# schematic.net
KiCad netlist of a schematic drawn in EAGLE
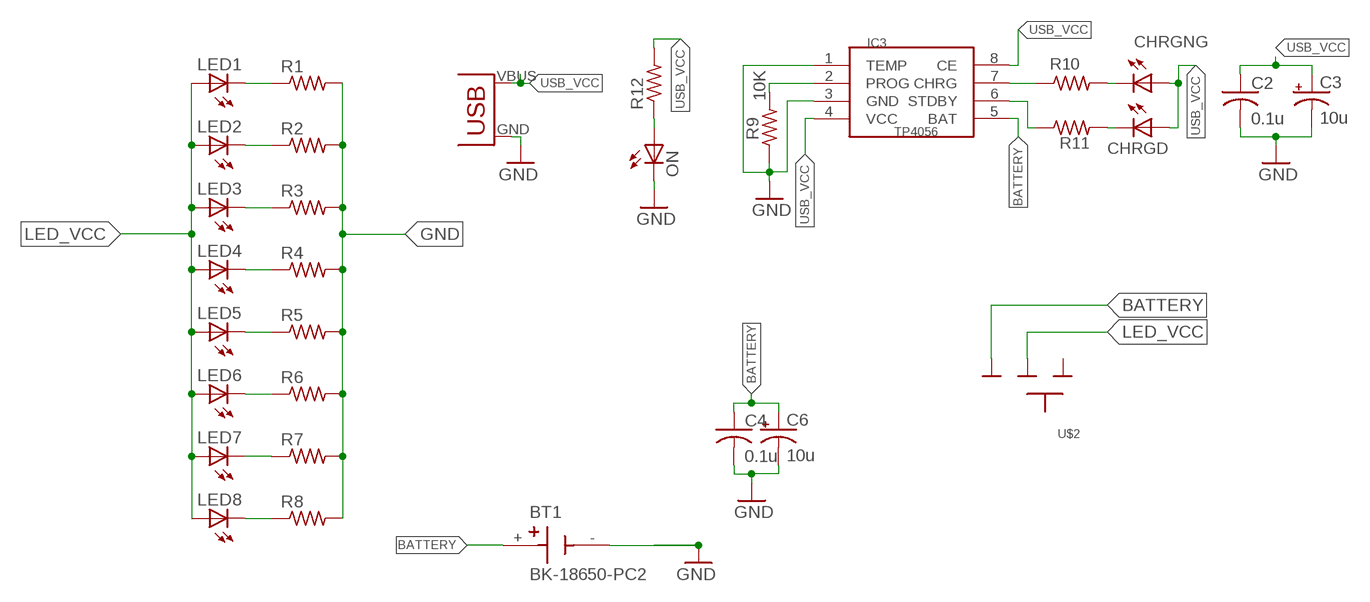
[diagram p0: schematic, sheet 1]

(export (version "E")
  (design (tool "Eeschema 10.0.6"))
  (components
    (comp (ref "BT1")
      (value "BK-18650-PC2")
      (footprint "eagle-import:BAT_BK-18650-PC2")
      (fields (field (name "MF") "MPD (Memory Protection Devices)"))
      (libsource (lib "eagle-import") (part "BK-18650-PC2"))
    )
    (comp (ref "C2")
      (value "0.1u")
      (footprint "eagle-import:C0805")
      (libsource (lib "eagle-import") (part "CAP0805"))
    )
    (comp (ref "C3")
      (value "10u")
      (footprint "eagle-import:B_3528-21R")
      (libsource (lib "eagle-import") (part "CAP_POL_16V"))
    )
    (comp (ref "C4")
      (value "0.1u")
      (footprint "eagle-import:C0805")
      (libsource (lib "eagle-import") (part "CAP0805"))
    )
    (comp (ref "C6")
      (value "10u")
      (footprint "eagle-import:B_3528-21R")
      (libsource (lib "eagle-import") (part "CAP_POL_16V"))
    )
    (comp (ref "CHRGD")
      (value "LED3MM")
      (footprint "eagle-import:LED3MM")
      (libsource (lib "eagle-import") (part "LED3MM"))
    )
    (comp (ref "CHRGNG")
      (value "LED3MM")
      (footprint "eagle-import:LED3MM")
      (libsource (lib "eagle-import") (part "LED3MM"))
    )
    (comp (ref "IC3")
      (value "TP4056")
      (footprint "eagle-import:SOP-8")
      (libsource (lib "eagle-import") (part "TP4056"))
    )
    (comp (ref "LED1")
      (value "LED5MM")
      (footprint "eagle-import:LED5MM")
      (libsource (lib "eagle-import") (part "CEDT_JANUARY_2015_v6_LED5MM"))
    )
    (comp (ref "LED2")
      (value "LED5MM")
      (footprint "eagle-import:LED5MM")
      (libsource (lib "eagle-import") (part "CEDT_JANUARY_2015_v6_LED5MM"))
    )
    (comp (ref "LED3")
      (value "LED5MM")
      (footprint "eagle-import:LED5MM")
      (libsource (lib "eagle-import") (part "CEDT_JANUARY_2015_v6_LED5MM"))
    )
    (comp (ref "LED4")
      (value "LED5MM")
      (footprint "eagle-import:LED5MM")
      (libsource (lib "eagle-import") (part "CEDT_JANUARY_2015_v6_LED5MM"))
    )
    (comp (ref "LED5")
      (value "LED5MM")
      (footprint "eagle-import:LED5MM")
      (libsource (lib "eagle-import") (part "CEDT_JANUARY_2015_v6_LED5MM"))
    )
    (comp (ref "LED6")
      (value "LED5MM")
      (footprint "eagle-import:LED5MM")
      (libsource (lib "eagle-import") (part "CEDT_JANUARY_2015_v6_LED5MM"))
    )
    (comp (ref "LED7")
      (value "LED5MM")
      (footprint "eagle-import:LED5MM")
      (libsource (lib "eagle-import") (part "CEDT_JANUARY_2015_v6_LED5MM"))
    )
    (comp (ref "LED8")
      (value "LED5MM")
      (footprint "eagle-import:LED5MM")
      (libsource (lib "eagle-import") (part "CEDT_JANUARY_2015_v6_LED5MM"))
    )
    (comp (ref "ON")
      (value "LED3MM")
      (footprint "eagle-import:LED3MM")
      (libsource (lib "eagle-import") (part "CEDT_LED3MM"))
    )
    (comp (ref "R1")
      (value "RESISTOR0207/7")
      (footprint "eagle-import:0207_7")
      (libsource (lib "eagle-import") (part "CEDT_JANUARY_2015_v6_RESISTOR0207/7"))
    )
    (comp (ref "R2")
      (value "RESISTOR0207/7")
      (footprint "eagle-import:0207_7")
      (libsource (lib "eagle-import") (part "CEDT_JANUARY_2015_v6_RESISTOR0207/7"))
    )
    (comp (ref "R3")
      (value "RESISTOR0207/7")
      (footprint "eagle-import:0207_7")
      (libsource (lib "eagle-import") (part "CEDT_JANUARY_2015_v6_RESISTOR0207/7"))
    )
    (comp (ref "R4")
      (value "RESISTOR0207/7")
      (footprint "eagle-import:0207_7")
      (libsource (lib "eagle-import") (part "CEDT_JANUARY_2015_v6_RESISTOR0207/7"))
    )
    (comp (ref "R5")
      (value "RESISTOR0207/7")
      (footprint "eagle-import:0207_7")
      (libsource (lib "eagle-import") (part "CEDT_JANUARY_2015_v6_RESISTOR0207/7"))
    )
    (comp (ref "R6")
      (value "RESISTOR0207/7")
      (footprint "eagle-import:0207_7")
      (libsource (lib "eagle-import") (part "CEDT_JANUARY_2015_v6_RESISTOR0207/7"))
    )
    (comp (ref "R7")
      (value "RESISTOR0207/7")
      (footprint "eagle-import:0207_7")
      (libsource (lib "eagle-import") (part "CEDT_JANUARY_2015_v6_RESISTOR0207/7"))
    )
    (comp (ref "R8")
      (value "RESISTOR0207/7")
      (footprint "eagle-import:0207_7")
      (libsource (lib "eagle-import") (part "CEDT_JANUARY_2015_v6_RESISTOR0207/7"))
    )
    (comp (ref "R9")
      (value "10K")
      (footprint "eagle-import:0207_7")
      (libsource (lib "eagle-import") (part "CEDT_JANUARY_2015_v5_RESISTOR0207/7"))
    )
    (comp (ref "R10")
      (value "470")
      (footprint "eagle-import:0207_7")
      (libsource (lib "eagle-import") (part "CEDT_JANUARY_2015_v5_RESISTOR0207/7"))
    )
    (comp (ref "R11")
      (value "470")
      (footprint "eagle-import:0207_7")
      (libsource (lib "eagle-import") (part "CEDT_JANUARY_2015_v5_RESISTOR0207/7"))
    )
    (comp (ref "R12")
      (value "RESISTOR0207/7")
      (footprint "eagle-import:0207_7")
      (libsource (lib "eagle-import") (part "RESISTOR0207/7"))
    )
    (comp (ref "U$1")
      (value "USB(POWER)")
      (footprint "eagle-import:USB(POWER)")
      (libsource (lib "eagle-import") (part "USB(POWER)"))
    )
    (comp (ref "U$2")
      (value "SLIDESWITCH-SMALL")
      (footprint "eagle-import:SMALLSWITCH")
      (libsource (lib "eagle-import") (part "SLIDESWITCH-SMALL"))
    )
  )
  (nets
    (net (code "1") (name "BATTERY") (class "Default")
      (node (ref "BT1") (pin "+") (pinfunction "+_+") (pintype "passive"))
      (node (ref "C4") (pin "1") (pinfunction "1_1") (pintype "passive"))
      (node (ref "C6") (pin "+") (pinfunction "+_+") (pintype "passive"))
      (node (ref "IC3") (pin "5") (pinfunction "BAT_5") (pintype "bidirectional"))
      (node (ref "U$2") (pin "3") (pinfunction "3_3") (pintype "bidirectional"))
    )
    (net (code "2") (name "GND") (class "Default")
      (node (ref "BT1") (pin "-") (pinfunction "-_-") (pintype "passive"))
      (node (ref "C2") (pin "2") (pinfunction "2_2") (pintype "passive"))
      (node (ref "C3") (pin "-") (pinfunction "-_-") (pintype "passive"))
      (node (ref "C4") (pin "2") (pinfunction "2_2") (pintype "passive"))
      (node (ref "C6") (pin "-") (pinfunction "-_-") (pintype "passive"))
      (node (ref "IC3") (pin "1") (pinfunction "TEMP_1") (pintype "bidirectional"))
      (node (ref "IC3") (pin "3") (pinfunction "GND_3") (pintype "bidirectional"))
      (node (ref "ON") (pin "K") (pinfunction "C_K") (pintype "passive"))
      (node (ref "R1") (pin "2") (pinfunction "2_2") (pintype "passive"))
      (node (ref "R2") (pin "2") (pinfunction "2_2") (pintype "passive"))
      (node (ref "R3") (pin "2") (pinfunction "2_2") (pintype "passive"))
      (node (ref "R4") (pin "2") (pinfunction "2_2") (pintype "passive"))
      (node (ref "R5") (pin "2") (pinfunction "2_2") (pintype "passive"))
      (node (ref "R6") (pin "2") (pinfunction "2_2") (pintype "passive"))
      (node (ref "R7") (pin "2") (pinfunction "2_2") (pintype "passive"))
      (node (ref "R8") (pin "2") (pinfunction "2_2") (pintype "passive"))
      (node (ref "R9") (pin "1") (pinfunction "1_1") (pintype "passive"))
      (node (ref "U$1") (pin "GND") (pinfunction "GND_GND") (pintype "power_in"))
    )
    (net (code "3") (name "LED_VCC") (class "Default")
      (node (ref "LED1") (pin "A") (pinfunction "A_A") (pintype "passive"))
      (node (ref "LED2") (pin "A") (pinfunction "A_A") (pintype "passive"))
      (node (ref "LED3") (pin "A") (pinfunction "A_A") (pintype "passive"))
      (node (ref "LED4") (pin "A") (pinfunction "A_A") (pintype "passive"))
      (node (ref "LED5") (pin "A") (pinfunction "A_A") (pintype "passive"))
      (node (ref "LED6") (pin "A") (pinfunction "A_A") (pintype "passive"))
      (node (ref "LED7") (pin "A") (pinfunction "A_A") (pintype "passive"))
      (node (ref "LED8") (pin "A") (pinfunction "A_A") (pintype "passive"))
      (node (ref "U$2") (pin "2") (pinfunction "2_2") (pintype "bidirectional"))
    )
    (net (code "4") (name "Net-(CHRGD-C)") (class "Default")
      (node (ref "CHRGD") (pin "K") (pinfunction "C_K") (pintype "passive"))
      (node (ref "R11") (pin "2") (pinfunction "2_2") (pintype "passive"))
    )
    (net (code "5") (name "Net-(CHRGNG-C)") (class "Default")
      (node (ref "CHRGNG") (pin "K") (pinfunction "C_K") (pintype "passive"))
      (node (ref "R10") (pin "2") (pinfunction "2_2") (pintype "passive"))
    )
    (net (code "6") (name "Net-(IC3-CHRG)") (class "Default")
      (node (ref "IC3") (pin "7") (pinfunction "CHRG_7") (pintype "bidirectional"))
      (node (ref "R10") (pin "1") (pinfunction "1_1") (pintype "passive"))
    )
    (net (code "7") (name "Net-(IC3-PROG)") (class "Default")
      (node (ref "IC3") (pin "2") (pinfunction "PROG_2") (pintype "bidirectional"))
      (node (ref "R9") (pin "2") (pinfunction "2_2") (pintype "passive"))
    )
    (net (code "8") (name "Net-(IC3-STDBY)") (class "Default")
      (node (ref "IC3") (pin "6") (pinfunction "STDBY_6") (pintype "bidirectional"))
      (node (ref "R11") (pin "1") (pinfunction "1_1") (pintype "passive"))
    )
    (net (code "9") (name "Net-(LED1-C)") (class "Default")
      (node (ref "LED1") (pin "K") (pinfunction "C_K") (pintype "passive"))
      (node (ref "R1") (pin "1") (pinfunction "1_1") (pintype "passive"))
    )
    (net (code "10") (name "Net-(LED2-C)") (class "Default")
      (node (ref "LED2") (pin "K") (pinfunction "C_K") (pintype "passive"))
      (node (ref "R2") (pin "1") (pinfunction "1_1") (pintype "passive"))
    )
    (net (code "11") (name "Net-(LED3-C)") (class "Default")
      (node (ref "LED3") (pin "K") (pinfunction "C_K") (pintype "passive"))
      (node (ref "R3") (pin "1") (pinfunction "1_1") (pintype "passive"))
    )
    (net (code "12") (name "Net-(LED4-C)") (class "Default")
      (node (ref "LED4") (pin "K") (pinfunction "C_K") (pintype "passive"))
      (node (ref "R4") (pin "1") (pinfunction "1_1") (pintype "passive"))
    )
    (net (code "13") (name "Net-(LED5-C)") (class "Default")
      (node (ref "LED5") (pin "K") (pinfunction "C_K") (pintype "passive"))
      (node (ref "R5") (pin "1") (pinfunction "1_1") (pintype "passive"))
    )
    (net (code "14") (name "Net-(LED6-C)") (class "Default")
      (node (ref "LED6") (pin "K") (pinfunction "C_K") (pintype "passive"))
      (node (ref "R6") (pin "1") (pinfunction "1_1") (pintype "passive"))
    )
    (net (code "15") (name "Net-(LED7-C)") (class "Default")
      (node (ref "LED7") (pin "K") (pinfunction "C_K") (pintype "passive"))
      (node (ref "R7") (pin "1") (pinfunction "1_1") (pintype "passive"))
    )
    (net (code "16") (name "Net-(LED8-C)") (class "Default")
      (node (ref "LED8") (pin "K") (pinfunction "C_K") (pintype "passive"))
      (node (ref "R8") (pin "1") (pinfunction "1_1") (pintype "passive"))
    )
    (net (code "17") (name "Net-(ON-PadA)") (class "Default")
      (node (ref "ON") (pin "A") (pinfunction "A_A") (pintype "passive"))
      (node (ref "R12") (pin "1") (pinfunction "1_1") (pintype "passive"))
    )
    (net (code "18") (name "USB_VCC") (class "Default")
      (node (ref "C2") (pin "1") (pinfunction "1_1") (pintype "passive"))
      (node (ref "C3") (pin "+") (pinfunction "+_+") (pintype "passive"))
      (node (ref "CHRGD") (pin "A") (pinfunction "A_A") (pintype "passive"))
      (node (ref "CHRGNG") (pin "A") (pinfunction "A_A") (pintype "passive"))
      (node (ref "IC3") (pin "4") (pinfunction "VCC_4") (pintype "bidirectional"))
      (node (ref "IC3") (pin "8") (pinfunction "CE_8") (pintype "bidirectional"))
      (node (ref "R12") (pin "2") (pinfunction "2_2") (pintype "passive"))
      (node (ref "U$1") (pin "VBUS") (pinfunction "VCC_VBUS") (pintype "power_in"))
    )
    (net (code "19") (name "unconnected-(U$2-Pad1)") (class "Default")
      (node (ref "U$2") (pin "1") (pinfunction "1_1") (pintype "bidirectional"))
    )
  )
)
